# Apex_CV_Expander_3U_v1_0.net
KiCad netlist of a schematic drawn in EAGLE
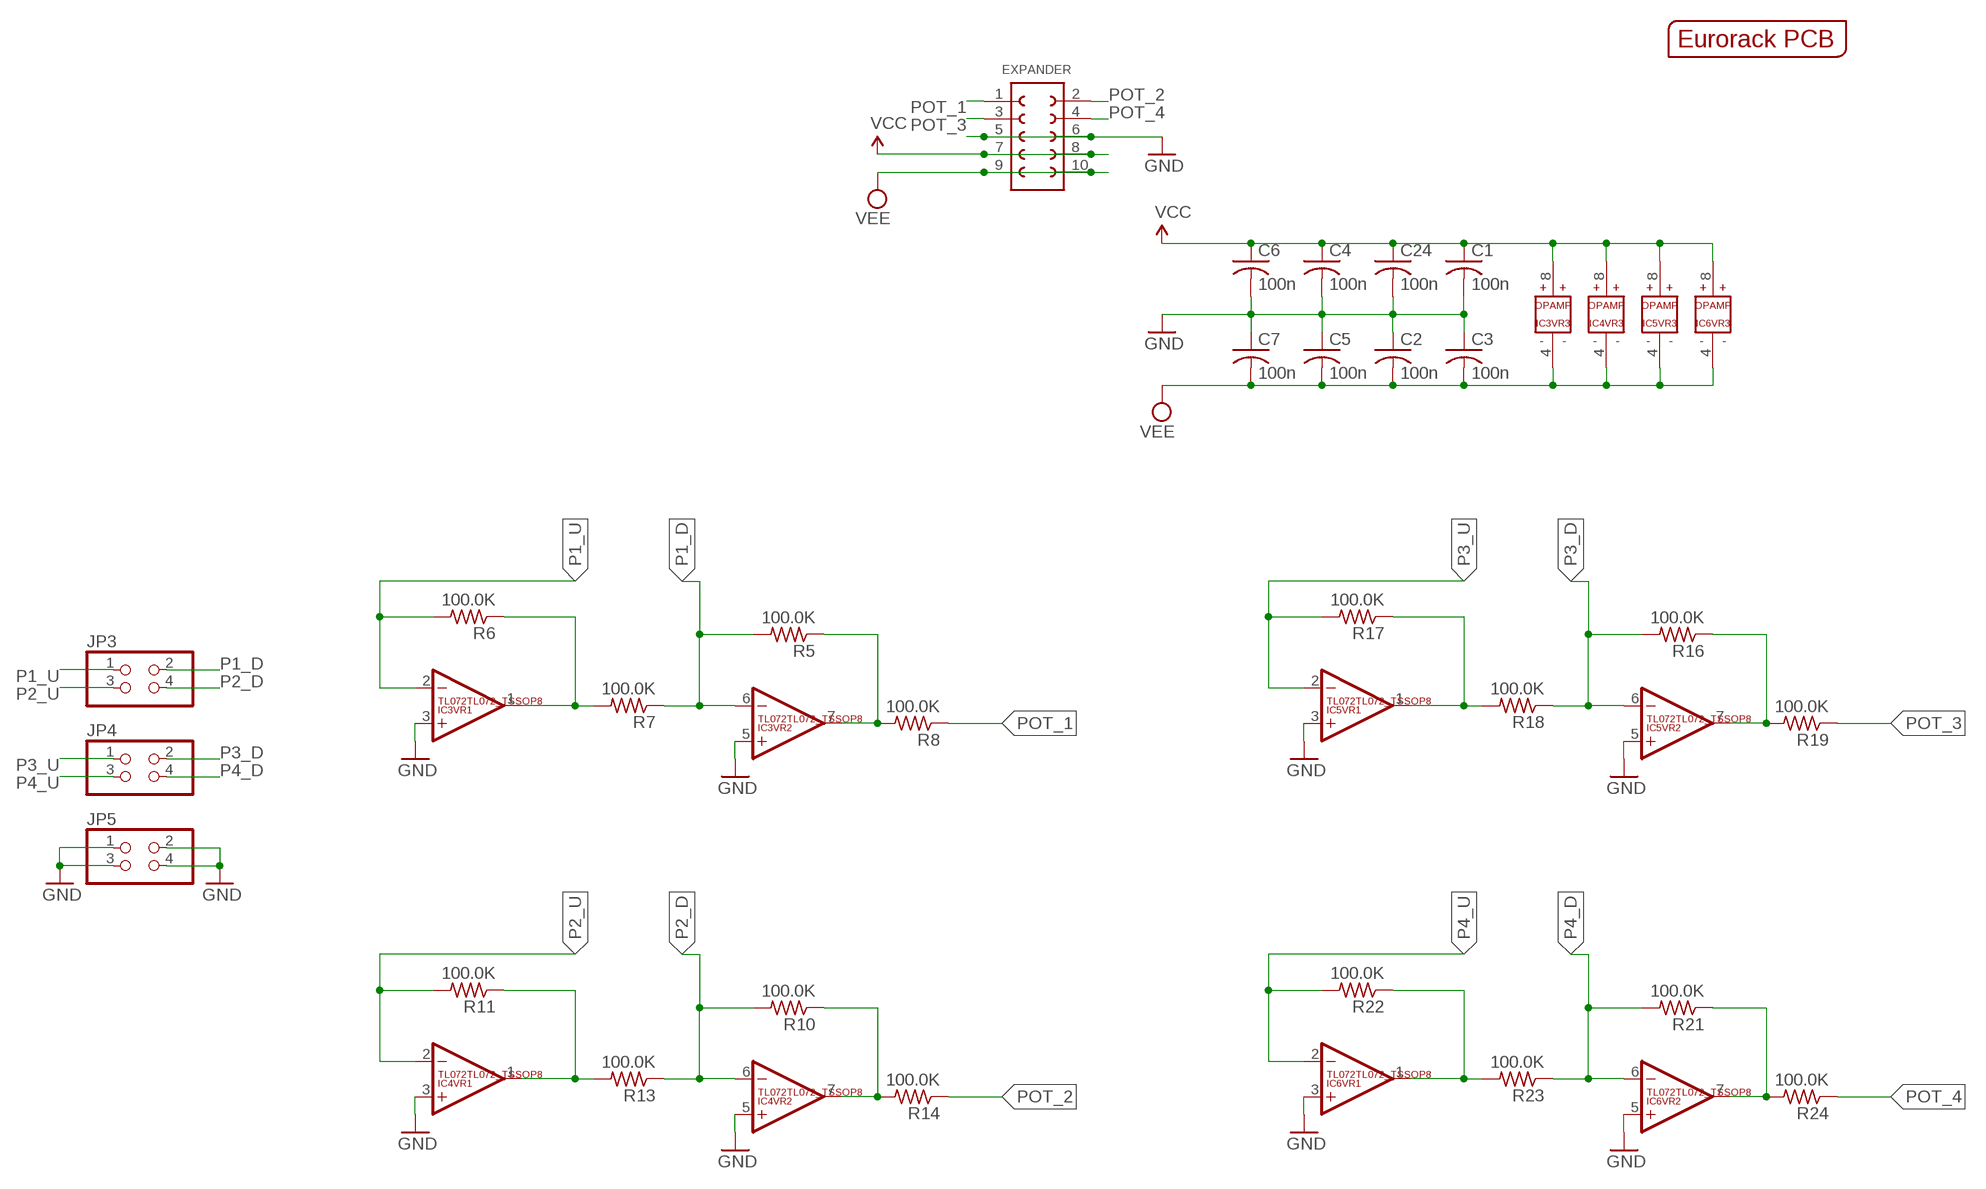
[diagram p0: schematic, sheet 1]

(export (version "E")
  (design (tool "Eeschema 10.0.6"))
  (components
    (comp (ref "C1")
      (value "100n")
      (footprint "eagle-import:C0603")
      (libsource (lib "eagle-import") (part "C-USC0603"))
    )
    (comp (ref "C2")
      (value "100n")
      (footprint "eagle-import:C0603")
      (libsource (lib "eagle-import") (part "C-USC0603"))
    )
    (comp (ref "C3")
      (value "100n")
      (footprint "eagle-import:C0603")
      (libsource (lib "eagle-import") (part "C-USC0603"))
    )
    (comp (ref "C4")
      (value "100n")
      (footprint "eagle-import:C0603")
      (libsource (lib "eagle-import") (part "C-USC0603"))
    )
    (comp (ref "C5")
      (value "100n")
      (footprint "eagle-import:C0603")
      (libsource (lib "eagle-import") (part "C-USC0603"))
    )
    (comp (ref "C6")
      (value "100n")
      (footprint "eagle-import:C0603")
      (libsource (lib "eagle-import") (part "C-USC0603"))
    )
    (comp (ref "C7")
      (value "100n")
      (footprint "eagle-import:C0603")
      (libsource (lib "eagle-import") (part "C-USC0603"))
    )
    (comp (ref "C24")
      (value "100n")
      (footprint "eagle-import:C0603")
      (libsource (lib "eagle-import") (part "C-USC0603"))
    )
    (comp (ref "EXPANDER")
      (value "61301021121")
      (footprint "eagle-import:61301021121")
      (libsource (lib "eagle-import") (part "61301021121"))
    )
    (comp (ref "IC3")
      (value "TL072TL072_TSSOP8")
      (footprint "eagle-import:TL072_TSSOP8")
      (libsource (lib "eagle-import") (part "TL072TL072_TSSOP8"))
    )
    (comp (ref "IC4")
      (value "TL072TL072_TSSOP8")
      (footprint "eagle-import:TL072_TSSOP8")
      (libsource (lib "eagle-import") (part "TL072TL072_TSSOP8"))
    )
    (comp (ref "IC5")
      (value "TL072TL072_TSSOP8")
      (footprint "eagle-import:TL072_TSSOP8")
      (libsource (lib "eagle-import") (part "TL072TL072_TSSOP8"))
    )
    (comp (ref "IC6")
      (value "TL072TL072_TSSOP8")
      (footprint "eagle-import:TL072_TSSOP8")
      (libsource (lib "eagle-import") (part "TL072TL072_TSSOP8"))
    )
    (comp (ref "JP3")
      (value "PINHD-2X2")
      (footprint "eagle-import:2X02")
      (libsource (lib "eagle-import") (part "PINHD-2X2"))
    )
    (comp (ref "JP4")
      (value "PINHD-2X2")
      (footprint "eagle-import:2X02")
      (libsource (lib "eagle-import") (part "PINHD-2X2"))
    )
    (comp (ref "JP5")
      (value "PINHD-2X2")
      (footprint "eagle-import:2X02")
      (libsource (lib "eagle-import") (part "PINHD-2X2"))
    )
    (comp (ref "PCB1")
      (value "EURORACK_PCB2HP")
      (footprint "eagle-import:EURORACK2HPPCB")
      (libsource (lib "eagle-import") (part "EURORACK_PCB2HP"))
    )
    (comp (ref "R5")
      (value "100.0K")
      (footprint "eagle-import:R0603")
      (libsource (lib "eagle-import") (part "R-US_R0603"))
    )
    (comp (ref "R6")
      (value "100.0K")
      (footprint "eagle-import:R0603")
      (libsource (lib "eagle-import") (part "R-US_R0603"))
    )
    (comp (ref "R7")
      (value "100.0K")
      (footprint "eagle-import:R0603")
      (libsource (lib "eagle-import") (part "R-US_R0603"))
    )
    (comp (ref "R8")
      (value "100.0K")
      (footprint "eagle-import:R0603")
      (libsource (lib "eagle-import") (part "R-US_R0603"))
    )
    (comp (ref "R10")
      (value "100.0K")
      (footprint "eagle-import:R0603")
      (libsource (lib "eagle-import") (part "R-US_R0603"))
    )
    (comp (ref "R11")
      (value "100.0K")
      (footprint "eagle-import:R0603")
      (libsource (lib "eagle-import") (part "R-US_R0603"))
    )
    (comp (ref "R13")
      (value "100.0K")
      (footprint "eagle-import:R0603")
      (libsource (lib "eagle-import") (part "R-US_R0603"))
    )
    (comp (ref "R14")
      (value "100.0K")
      (footprint "eagle-import:R0603")
      (libsource (lib "eagle-import") (part "R-US_R0603"))
    )
    (comp (ref "R16")
      (value "100.0K")
      (footprint "eagle-import:R0603")
      (libsource (lib "eagle-import") (part "R-US_R0603"))
    )
    (comp (ref "R17")
      (value "100.0K")
      (footprint "eagle-import:R0603")
      (libsource (lib "eagle-import") (part "R-US_R0603"))
    )
    (comp (ref "R18")
      (value "100.0K")
      (footprint "eagle-import:R0603")
      (libsource (lib "eagle-import") (part "R-US_R0603"))
    )
    (comp (ref "R19")
      (value "100.0K")
      (footprint "eagle-import:R0603")
      (libsource (lib "eagle-import") (part "R-US_R0603"))
    )
    (comp (ref "R21")
      (value "100.0K")
      (footprint "eagle-import:R0603")
      (libsource (lib "eagle-import") (part "R-US_R0603"))
    )
    (comp (ref "R22")
      (value "100.0K")
      (footprint "eagle-import:R0603")
      (libsource (lib "eagle-import") (part "R-US_R0603"))
    )
    (comp (ref "R23")
      (value "100.0K")
      (footprint "eagle-import:R0603")
      (libsource (lib "eagle-import") (part "R-US_R0603"))
    )
    (comp (ref "R24")
      (value "100.0K")
      (footprint "eagle-import:R0603")
      (libsource (lib "eagle-import") (part "R-US_R0603"))
    )
  )
  (nets
    (net (code "1") (name "GND") (class "Default")
      (node (ref "C1") (pin "2") (pinfunction "2_2") (pintype "passive"))
      (node (ref "C2") (pin "1") (pinfunction "1_1") (pintype "passive"))
      (node (ref "C24") (pin "2") (pinfunction "2_2") (pintype "passive"))
      (node (ref "C3") (pin "1") (pinfunction "1_1") (pintype "passive"))
      (node (ref "C4") (pin "2") (pinfunction "2_2") (pintype "passive"))
      (node (ref "C5") (pin "1") (pinfunction "1_1") (pintype "passive"))
      (node (ref "C6") (pin "2") (pinfunction "2_2") (pintype "passive"))
      (node (ref "C7") (pin "1") (pinfunction "1_1") (pintype "passive"))
      (node (ref "EXPANDER") (pin "5") (pinfunction "3_5") (pintype "passive"))
      (node (ref "EXPANDER") (pin "6") (pinfunction "8_6") (pintype "passive"))
      (node (ref "IC3") (pin "3") (pinfunction "+IN_3") (pintype "input"))
      (node (ref "IC3") (pin "5") (pinfunction "+IN_5") (pintype "input"))
      (node (ref "IC4") (pin "3") (pinfunction "+IN_3") (pintype "input"))
      (node (ref "IC4") (pin "5") (pinfunction "+IN_5") (pintype "input"))
      (node (ref "IC5") (pin "3") (pinfunction "+IN_3") (pintype "input"))
      (node (ref "IC5") (pin "5") (pinfunction "+IN_5") (pintype "input"))
      (node (ref "IC6") (pin "3") (pinfunction "+IN_3") (pintype "input"))
      (node (ref "IC6") (pin "5") (pinfunction "+IN_5") (pintype "input"))
      (node (ref "JP5") (pin "1") (pinfunction "1_1") (pintype "passive"))
      (node (ref "JP5") (pin "2") (pinfunction "2_2") (pintype "passive"))
      (node (ref "JP5") (pin "3") (pinfunction "3_3") (pintype "passive"))
      (node (ref "JP5") (pin "4") (pinfunction "4_4") (pintype "passive"))
    )
    (net (code "2") (name "Net-(IC3A-OUT)") (class "Default")
      (node (ref "IC3") (pin "1") (pinfunction "OUT_1") (pintype "output"))
      (node (ref "R6") (pin "1") (pinfunction "1_1") (pintype "passive"))
      (node (ref "R7") (pin "2") (pinfunction "2_2") (pintype "passive"))
    )
    (net (code "3") (name "Net-(IC3B-OUT)") (class "Default")
      (node (ref "IC3") (pin "7") (pinfunction "OUT_7") (pintype "output"))
      (node (ref "R5") (pin "1") (pinfunction "1_1") (pintype "passive"))
      (node (ref "R8") (pin "2") (pinfunction "2_2") (pintype "passive"))
    )
    (net (code "4") (name "Net-(IC4A-OUT)") (class "Default")
      (node (ref "IC4") (pin "1") (pinfunction "OUT_1") (pintype "output"))
      (node (ref "R11") (pin "1") (pinfunction "1_1") (pintype "passive"))
      (node (ref "R13") (pin "2") (pinfunction "2_2") (pintype "passive"))
    )
    (net (code "5") (name "Net-(IC4B-OUT)") (class "Default")
      (node (ref "IC4") (pin "7") (pinfunction "OUT_7") (pintype "output"))
      (node (ref "R10") (pin "1") (pinfunction "1_1") (pintype "passive"))
      (node (ref "R14") (pin "2") (pinfunction "2_2") (pintype "passive"))
    )
    (net (code "6") (name "Net-(IC5A-OUT)") (class "Default")
      (node (ref "IC5") (pin "1") (pinfunction "OUT_1") (pintype "output"))
      (node (ref "R17") (pin "1") (pinfunction "1_1") (pintype "passive"))
      (node (ref "R18") (pin "2") (pinfunction "2_2") (pintype "passive"))
    )
    (net (code "7") (name "Net-(IC5B-OUT)") (class "Default")
      (node (ref "IC5") (pin "7") (pinfunction "OUT_7") (pintype "output"))
      (node (ref "R16") (pin "1") (pinfunction "1_1") (pintype "passive"))
      (node (ref "R19") (pin "2") (pinfunction "2_2") (pintype "passive"))
    )
    (net (code "8") (name "Net-(IC6A-OUT)") (class "Default")
      (node (ref "IC6") (pin "1") (pinfunction "OUT_1") (pintype "output"))
      (node (ref "R22") (pin "1") (pinfunction "1_1") (pintype "passive"))
      (node (ref "R23") (pin "2") (pinfunction "2_2") (pintype "passive"))
    )
    (net (code "9") (name "Net-(IC6B-OUT)") (class "Default")
      (node (ref "IC6") (pin "7") (pinfunction "OUT_7") (pintype "output"))
      (node (ref "R21") (pin "1") (pinfunction "1_1") (pintype "passive"))
      (node (ref "R24") (pin "2") (pinfunction "2_2") (pintype "passive"))
    )
    (net (code "10") (name "P1_D") (class "Default")
      (node (ref "IC3") (pin "6") (pinfunction "-IN_6") (pintype "input"))
      (node (ref "JP3") (pin "2") (pinfunction "2_2") (pintype "passive"))
      (node (ref "R5") (pin "2") (pinfunction "2_2") (pintype "passive"))
      (node (ref "R7") (pin "1") (pinfunction "1_1") (pintype "passive"))
    )
    (net (code "11") (name "P1_U") (class "Default")
      (node (ref "IC3") (pin "2") (pinfunction "-IN_2") (pintype "input"))
      (node (ref "JP3") (pin "1") (pinfunction "1_1") (pintype "passive"))
      (node (ref "R6") (pin "2") (pinfunction "2_2") (pintype "passive"))
    )
    (net (code "12") (name "P2_D") (class "Default")
      (node (ref "IC4") (pin "6") (pinfunction "-IN_6") (pintype "input"))
      (node (ref "JP3") (pin "4") (pinfunction "4_4") (pintype "passive"))
      (node (ref "R10") (pin "2") (pinfunction "2_2") (pintype "passive"))
      (node (ref "R13") (pin "1") (pinfunction "1_1") (pintype "passive"))
    )
    (net (code "13") (name "P2_U") (class "Default")
      (node (ref "IC4") (pin "2") (pinfunction "-IN_2") (pintype "input"))
      (node (ref "JP3") (pin "3") (pinfunction "3_3") (pintype "passive"))
      (node (ref "R11") (pin "2") (pinfunction "2_2") (pintype "passive"))
    )
    (net (code "14") (name "P3_D") (class "Default")
      (node (ref "IC5") (pin "6") (pinfunction "-IN_6") (pintype "input"))
      (node (ref "JP4") (pin "2") (pinfunction "2_2") (pintype "passive"))
      (node (ref "R16") (pin "2") (pinfunction "2_2") (pintype "passive"))
      (node (ref "R18") (pin "1") (pinfunction "1_1") (pintype "passive"))
    )
    (net (code "15") (name "P3_U") (class "Default")
      (node (ref "IC5") (pin "2") (pinfunction "-IN_2") (pintype "input"))
      (node (ref "JP4") (pin "1") (pinfunction "1_1") (pintype "passive"))
      (node (ref "R17") (pin "2") (pinfunction "2_2") (pintype "passive"))
    )
    (net (code "16") (name "P4_D") (class "Default")
      (node (ref "IC6") (pin "6") (pinfunction "-IN_6") (pintype "input"))
      (node (ref "JP4") (pin "4") (pinfunction "4_4") (pintype "passive"))
      (node (ref "R21") (pin "2") (pinfunction "2_2") (pintype "passive"))
      (node (ref "R23") (pin "1") (pinfunction "1_1") (pintype "passive"))
    )
    (net (code "17") (name "P4_U") (class "Default")
      (node (ref "IC6") (pin "2") (pinfunction "-IN_2") (pintype "input"))
      (node (ref "JP4") (pin "3") (pinfunction "3_3") (pintype "passive"))
      (node (ref "R22") (pin "2") (pinfunction "2_2") (pintype "passive"))
    )
    (net (code "18") (name "POT_1") (class "Default")
      (node (ref "EXPANDER") (pin "1") (pinfunction "1_1") (pintype "passive"))
      (node (ref "R8") (pin "1") (pinfunction "1_1") (pintype "passive"))
    )
    (net (code "19") (name "POT_2") (class "Default")
      (node (ref "EXPANDER") (pin "2") (pinfunction "10_2") (pintype "passive"))
      (node (ref "R14") (pin "1") (pinfunction "1_1") (pintype "passive"))
    )
    (net (code "20") (name "POT_3") (class "Default")
      (node (ref "EXPANDER") (pin "3") (pinfunction "2_3") (pintype "passive"))
      (node (ref "R19") (pin "1") (pinfunction "1_1") (pintype "passive"))
    )
    (net (code "21") (name "POT_4") (class "Default")
      (node (ref "EXPANDER") (pin "4") (pinfunction "9_4") (pintype "passive"))
      (node (ref "R24") (pin "1") (pinfunction "1_1") (pintype "passive"))
    )
    (net (code "22") (name "VCC") (class "Default")
      (node (ref "C1") (pin "1") (pinfunction "1_1") (pintype "passive"))
      (node (ref "C24") (pin "1") (pinfunction "1_1") (pintype "passive"))
      (node (ref "C4") (pin "1") (pinfunction "1_1") (pintype "passive"))
      (node (ref "C6") (pin "1") (pinfunction "1_1") (pintype "passive"))
      (node (ref "EXPANDER") (pin "7") (pinfunction "4_7") (pintype "passive"))
      (node (ref "EXPANDER") (pin "8") (pinfunction "7_8") (pintype "passive"))
      (node (ref "IC3") (pin "8") (pinfunction "V+_8") (pintype "power_in"))
      (node (ref "IC4") (pin "8") (pinfunction "V+_8") (pintype "power_in"))
      (node (ref "IC5") (pin "8") (pinfunction "V+_8") (pintype "power_in"))
      (node (ref "IC6") (pin "8") (pinfunction "V+_8") (pintype "power_in"))
    )
    (net (code "23") (name "VEE") (class "Default")
      (node (ref "C2") (pin "2") (pinfunction "2_2") (pintype "passive"))
      (node (ref "C3") (pin "2") (pinfunction "2_2") (pintype "passive"))
      (node (ref "C5") (pin "2") (pinfunction "2_2") (pintype "passive"))
      (node (ref "C7") (pin "2") (pinfunction "2_2") (pintype "passive"))
      (node (ref "EXPANDER") (pin "10") (pinfunction "6_10") (pintype "passive"))
      (node (ref "EXPANDER") (pin "9") (pinfunction "5_9") (pintype "passive"))
      (node (ref "IC3") (pin "4") (pinfunction "V-_4") (pintype "power_in"))
      (node (ref "IC4") (pin "4") (pinfunction "V-_4") (pintype "power_in"))
      (node (ref "IC5") (pin "4") (pinfunction "V-_4") (pintype "power_in"))
      (node (ref "IC6") (pin "4") (pinfunction "V-_4") (pintype "power_in"))
    )
  )
)
